# Out_Inputs.net
KiCad netlist of a schematic drawn in Altium Designer
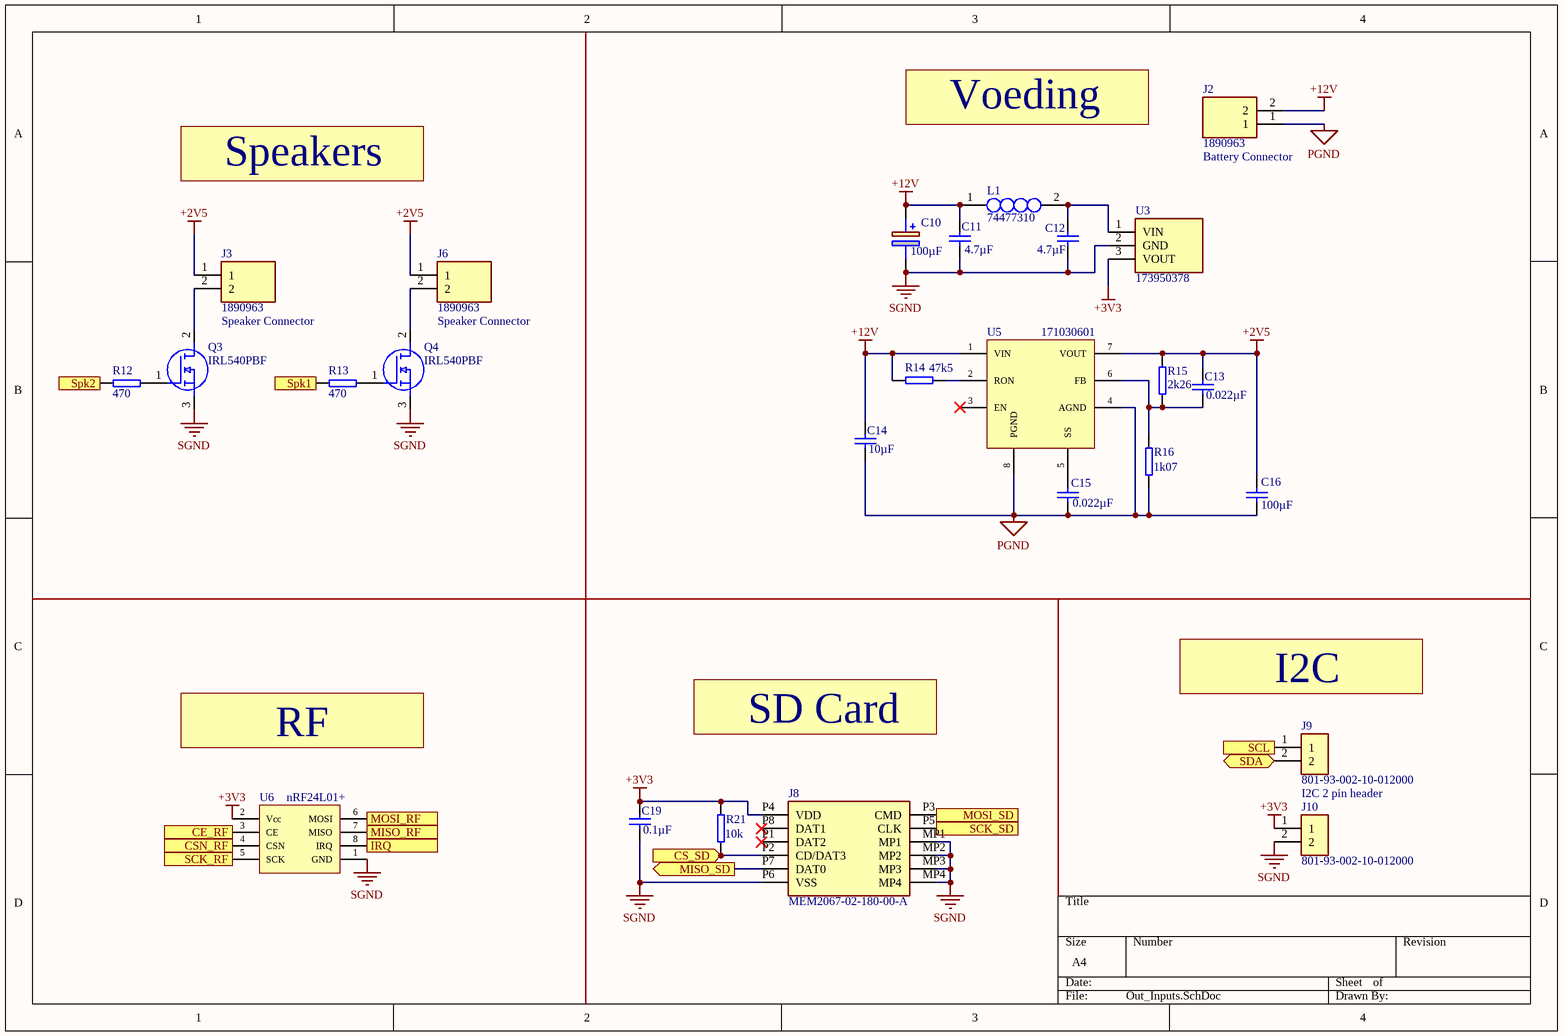
[diagram p0: Out_Inputs.SchDoc]

(export (version "E")
  (design (tool "Eeschema 10.0.6"))
  (components
    (comp (ref "C10")
      (value "100µF")
      (footprint "CAPPRD350W52D800H1300")
      (description "Wurth Elektronik 100uF 50 V dc Aluminium Electrolytic Capacitor")
      (fields
        (field (name "MOUSER PART NUMBER") "710-865080543009")
        (field (name "MANUFACTURER_PART_NUMBER") "865080543009")
      )
      (libsource (lib "Schematic_Lib") (part "860010674014"))
    )
    (comp (ref "C11")
      (value "4.7µF")
      (footprint "Capacitor 1206")
      (description "Capacitor")
      (libsource (lib "Schematic_Lib") (part "Capacitor 1206"))
    )
    (comp (ref "C12")
      (value "4.7µF")
      (footprint "Capacitor 1206")
      (description "Capacitor")
      (libsource (lib "Schematic_Lib") (part "Capacitor 1206"))
    )
    (comp (ref "C13")
      (value "0.022µF")
      (footprint "Capacitor 0603")
      (description "Capacitor")
      (libsource (lib "Schematic_Lib") (part "Capacitor 0603"))
    )
    (comp (ref "C14")
      (value "10µF")
      (footprint "Capacitor 0603")
      (description "Capacitor")
      (libsource (lib "Schematic_Lib") (part "Capacitor 0603"))
    )
    (comp (ref "C15")
      (value "0.022µF")
      (footprint "Capacitor 0603")
      (description "Capacitor")
      (libsource (lib "Schematic_Lib") (part "Capacitor 0603"))
    )
    (comp (ref "C16")
      (value "100µF")
      (footprint "Cap_1210")
      (description "Capacitor")
      (libsource (lib "Schematic_Lib") (part "Capacitor 1210"))
    )
    (comp (ref "C19")
      (value "0.1µF")
      (footprint "Capacitor 0603")
      (description "Capacitor")
      (libsource (lib "Schematic_Lib") (part "Capacitor 0603"))
    )
    (comp (ref "J2")
      (value "1890963")
      (footprint "1890963")
      (description "Connector: 2pin screw terminal")
      (fields (field (name "MOUSER PART NUMBER") "651-1890963"))
      (libsource (lib "") (part "1890963_1"))
    )
    (comp (ref "J3")
      (value "1890963")
      (footprint "1890963")
      (description "Connector: 2pin screw terminal")
      (fields (field (name "MOUSER PART NUMBER") "651-1890963"))
      (libsource (lib "Schematic_Lib") (part "1890963"))
    )
    (comp (ref "J6")
      (value "1890963")
      (footprint "1890963")
      (description "Connector: 2pin screw terminal")
      (fields (field (name "MOUSER PART NUMBER") "651-1890963"))
      (libsource (lib "Schematic_Lib") (part "1890963"))
    )
    (comp (ref "J8")
      (value "MEM2067-02-180-00-A")
      (footprint "MEM20670218000A")
      (fields (field (name "MOUSER PART NUMBER") "640-MEM20670218000A"))
      (libsource (lib "Schematic_Lib") (part "MEM2067-02-180-00-A"))
    )
    (comp (ref "J9")
      (value "801-93-002-10-012000")
      (footprint "801-93-002-10-012000")
      (description "2 pin header 2.54mm pitch")
      (libsource (lib "Schematic_Lib") (part "801-93-002-10-012000"))
    )
    (comp (ref "J10")
      (value "801-93-002-10-012000")
      (footprint "801-93-002-10-012000")
      (description "2 pin header 2.54mm pitch")
      (libsource (lib "Schematic_Lib") (part "801-93-002-10-012000"))
    )
    (comp (ref "L1")
      (value "74477310")
      (footprint "WE-PD2_453255")
      (description "Inductor")
      (fields
        (field (name "MANUFACTURER_PART_NUMBER") "7447730")
        (field (name "MOUSER PART NUMBER") "710-7447730")
      )
      (libsource (lib "Schematic_Lib") (part "7447730"))
    )
    (comp (ref "Q3")
      (value "IRL540PBF")
      (footprint "TO-220-3")
      (description "MOSFET N-CH  100V HEXFET MOSFET")
      (fields (field (name "MOUSER PART NUMBER") "844-IRL540PBF"))
      (libsource (lib "Schematic_Lib") (part "IRL540PBF"))
    )
    (comp (ref "Q4")
      (value "IRL540PBF")
      (footprint "TO-220-3")
      (description "MOSFET N-CH  100V HEXFET MOSFET")
      (fields (field (name "MOUSER PART NUMBER") "844-IRL540PBF"))
      (libsource (lib "Schematic_Lib") (part "IRL540PBF"))
    )
    (comp (ref "R12")
      (value "470")
      (footprint "Resistor 0603")
      (description "Resistor")
      (libsource (lib "Schematic_Lib") (part "Resistor 0603"))
    )
    (comp (ref "R13")
      (value "470")
      (footprint "Resistor 0603")
      (description "Resistor")
      (libsource (lib "Schematic_Lib") (part "Resistor 0603"))
    )
    (comp (ref "R14")
      (value "47k5")
      (footprint "Resistor 0603")
      (description "Resistor")
      (libsource (lib "Schematic_Lib") (part "Resistor 0603"))
    )
    (comp (ref "R15")
      (value "2k26")
      (footprint "Resistor 0603")
      (description "Resistor")
      (libsource (lib "Schematic_Lib") (part "Resistor 0603"))
    )
    (comp (ref "R16")
      (value "1k07")
      (footprint "Resistor 0603")
      (description "Resistor")
      (libsource (lib "Schematic_Lib") (part "Resistor 0603"))
    )
    (comp (ref "R21")
      (value "10k")
      (footprint "Resistor 0603")
      (description "Resistor")
      (libsource (lib "Schematic_Lib") (part "Resistor 0603"))
    )
    (comp (ref "U3")
      (value "173950378")
      (footprint "173950378")
      (description "MagI3C Power Module 0.5A 3.3V 6-28V SIP3")
      (fields (field (name "MOUSER PART NUMBER") "710-173950378"))
      (libsource (lib "Schematic_Lib") (part "173950378"))
    )
    (comp (ref "U5")
      (value "171030601")
      (footprint "TO263-7EP")
      (description "MagI3C-VDRM Variable Step Down Regulator Module, TO263-7EP, 6-42Vin, 3Aout")
      (fields (field (name "MANUFACTURER") "Wurth Electronics"))
      (libsource (lib "Schematic_Lib") (part "CMP-533-000007-A.2"))
    )
    (comp (ref "U6")
      (value "nRF24L01+")
      (footprint "nRF24L01+")
      (libsource (lib "Schematic_Lib") (part "nRF24L01+"))
    )
  )
  (nets
    (net (code "1") (name "+2V5") (class "Default")
      (node (ref "C13") (pin "1") (pinfunction "1_1") (pintype "passive"))
      (node (ref "C16") (pin "2") (pinfunction "2_2") (pintype "passive"))
      (node (ref "J3") (pin "1") (pinfunction "1_1") (pintype "passive"))
      (node (ref "J6") (pin "1") (pinfunction "1_1") (pintype "passive"))
      (node (ref "R15") (pin "1") (pintype "passive"))
      (node (ref "U5") (pin "7") (pinfunction "VOUT_7") (pintype "passive"))
    )
    (net (code "2") (name "+3V3") (class "Default")
      (node (ref "C19") (pin "1") (pinfunction "1_1") (pintype "passive"))
      (node (ref "J10") (pin "1") (pinfunction "1_1") (pintype "passive"))
      (node (ref "J8") (pin "P4") (pinfunction "VDD_P4") (pintype "passive"))
      (node (ref "R21") (pin "1") (pintype "passive"))
      (node (ref "U3") (pin "3") (pinfunction "VOUT_3") (pintype "passive"))
      (node (ref "U6") (pin "2") (pinfunction "Vcc_2") (pintype "passive"))
    )
    (net (code "3") (name "+12V") (class "Default")
      (node (ref "C10") (pin "1") (pinfunction "+_1") (pintype "passive"))
      (node (ref "C11") (pin "1") (pinfunction "1_1") (pintype "passive"))
      (node (ref "C14") (pin "1") (pinfunction "1_1") (pintype "passive"))
      (node (ref "J2") (pin "2") (pinfunction "2_2") (pintype "passive"))
      (node (ref "L1") (pin "1") (pinfunction "1_1") (pintype "passive"))
      (node (ref "R14") (pin "1") (pintype "passive"))
      (node (ref "U5") (pin "1") (pinfunction "VIN_1") (pintype "passive"))
    )
    (net (code "4") (name "/CE_RF") (class "Default")
      (node (ref "U6") (pin "3") (pinfunction "CE_3") (pintype "passive"))
    )
    (net (code "5") (name "/CSN_RF") (class "Default")
      (node (ref "U6") (pin "4") (pinfunction "CSN_4") (pintype "passive"))
    )
    (net (code "6") (name "/CS_SD") (class "Default")
      (node (ref "J8") (pin "P2") (pinfunction "CD/DAT3_P2") (pintype "passive"))
      (node (ref "R21") (pin "2") (pintype "passive"))
    )
    (net (code "7") (name "/IRQ") (class "Default")
      (node (ref "U6") (pin "8") (pinfunction "IRQ_8") (pintype "passive"))
    )
    (net (code "8") (name "/MISO_RF") (class "Default")
      (node (ref "U6") (pin "7") (pinfunction "MISO_7") (pintype "passive"))
    )
    (net (code "9") (name "/MISO_SD") (class "Default")
      (node (ref "J8") (pin "P7") (pinfunction "DAT0_P7") (pintype "passive"))
    )
    (net (code "10") (name "/MOSI_RF") (class "Default")
      (node (ref "U6") (pin "6") (pinfunction "MOSI_6") (pintype "passive"))
    )
    (net (code "11") (name "/MOSI_SD") (class "Default")
      (node (ref "J8") (pin "P3") (pinfunction "CMD_P3") (pintype "passive"))
    )
    (net (code "12") (name "/SCK_RF") (class "Default")
      (node (ref "U6") (pin "5") (pinfunction "SCK_5") (pintype "passive"))
    )
    (net (code "13") (name "/SCK_SD") (class "Default")
      (node (ref "J8") (pin "P5") (pinfunction "CLK_P5") (pintype "passive"))
    )
    (net (code "14") (name "/SCL") (class "Default")
      (node (ref "J9") (pin "1") (pinfunction "1_1") (pintype "passive"))
    )
    (net (code "15") (name "/SDA") (class "Default")
      (node (ref "J9") (pin "2") (pinfunction "2_2") (pintype "passive"))
    )
    (net (code "16") (name "/Spk1") (class "Default") (node (ref "R13") (pin "1") (pintype "passive")))
    (net (code "17") (name "/Spk2") (class "Default") (node (ref "R12") (pin "1") (pintype "passive")))
    (net (code "18") (name "Net-(Q3-D)") (class "Default")
      (node (ref "J3") (pin "2") (pinfunction "2_2") (pintype "passive"))
      (node (ref "Q3") (pin "2") (pinfunction "D_2") (pintype "passive"))
    )
    (net (code "19") (name "Net-(Q3-G)") (class "Default")
      (node (ref "Q3") (pin "1") (pinfunction "G_1") (pintype "passive"))
      (node (ref "R12") (pin "2") (pintype "passive"))
    )
    (net (code "20") (name "Net-(Q4-D)") (class "Default")
      (node (ref "J6") (pin "2") (pinfunction "2_2") (pintype "passive"))
      (node (ref "Q4") (pin "2") (pinfunction "D_2") (pintype "passive"))
    )
    (net (code "21") (name "Net-(Q4-G)") (class "Default")
      (node (ref "Q4") (pin "1") (pinfunction "G_1") (pintype "passive"))
      (node (ref "R13") (pin "2") (pintype "passive"))
    )
    (net (code "22") (name "Net-(U3-VIN)") (class "Default")
      (node (ref "C12") (pin "1") (pinfunction "1_1") (pintype "passive"))
      (node (ref "L1") (pin "2") (pinfunction "2_2") (pintype "passive"))
      (node (ref "U3") (pin "1") (pinfunction "VIN_1") (pintype "passive"))
    )
    (net (code "23") (name "Net-(U5-FB)") (class "Default")
      (node (ref "C13") (pin "2") (pinfunction "2_2") (pintype "passive"))
      (node (ref "R15") (pin "2") (pintype "passive"))
      (node (ref "R16") (pin "1") (pintype "passive"))
      (node (ref "U5") (pin "6") (pinfunction "FB_6") (pintype "passive"))
    )
    (net (code "24") (name "Net-(U5-RON)") (class "Default")
      (node (ref "R14") (pin "2") (pintype "passive"))
      (node (ref "U5") (pin "2") (pinfunction "RON_2") (pintype "passive"))
    )
    (net (code "25") (name "Net-(U5-SS)") (class "Default")
      (node (ref "C15") (pin "2") (pinfunction "2_2") (pintype "passive"))
      (node (ref "U5") (pin "5") (pinfunction "SS_5") (pintype "passive"))
    )
    (net (code "26") (name "PGND") (class "Default")
      (node (ref "C14") (pin "2") (pinfunction "2_2") (pintype "passive"))
      (node (ref "C15") (pin "1") (pinfunction "1_1") (pintype "passive"))
      (node (ref "C16") (pin "1") (pinfunction "1_1") (pintype "passive"))
      (node (ref "J2") (pin "1") (pinfunction "1_1") (pintype "passive"))
      (node (ref "R16") (pin "2") (pintype "passive"))
      (node (ref "U5") (pin "4") (pinfunction "AGND_4") (pintype "passive"))
      (node (ref "U5") (pin "8") (pinfunction "PGND_8") (pintype "passive"))
    )
    (net (code "27") (name "SGND") (class "Default")
      (node (ref "C10") (pin "2") (pinfunction "-_2") (pintype "passive"))
      (node (ref "C11") (pin "2") (pinfunction "2_2") (pintype "passive"))
      (node (ref "C12") (pin "2") (pinfunction "2_2") (pintype "passive"))
      (node (ref "C19") (pin "2") (pinfunction "2_2") (pintype "passive"))
      (node (ref "J10") (pin "2") (pinfunction "2_2") (pintype "passive"))
      (node (ref "J8") (pin "MP1") (pinfunction "MP1_MP1") (pintype "passive"))
      (node (ref "J8") (pin "MP2") (pinfunction "MP2_MP2") (pintype "passive"))
      (node (ref "J8") (pin "MP3") (pinfunction "MP3_MP3") (pintype "passive"))
      (node (ref "J8") (pin "MP4") (pinfunction "MP4_MP4") (pintype "passive"))
      (node (ref "J8") (pin "P6") (pinfunction "VSS_P6") (pintype "passive"))
      (node (ref "Q3") (pin "3") (pinfunction "S_3") (pintype "passive"))
      (node (ref "Q4") (pin "3") (pinfunction "S_3") (pintype "passive"))
      (node (ref "U3") (pin "2") (pinfunction "GND_2") (pintype "passive"))
      (node (ref "U6") (pin "1") (pinfunction "GND_1") (pintype "passive"))
    )
    (net (code "28") (name "unconnected-(J8-DAT1-PadP8)") (class "Default")
      (node (ref "J8") (pin "P8") (pinfunction "DAT1_P8") (pintype "passive+no_connect"))
    )
    (net (code "29") (name "unconnected-(J8-DAT2-PadP1)") (class "Default")
      (node (ref "J8") (pin "P1") (pinfunction "DAT2_P1") (pintype "passive+no_connect"))
    )
    (net (code "30") (name "unconnected-(U5-EN-Pad3)") (class "Default")
      (node (ref "U5") (pin "3") (pinfunction "EN_3") (pintype "passive+no_connect"))
    )
  )
)
